# RF_And_SD_Ticketing_Master.net
KiCad netlist of a schematic drawn in Altium Designer
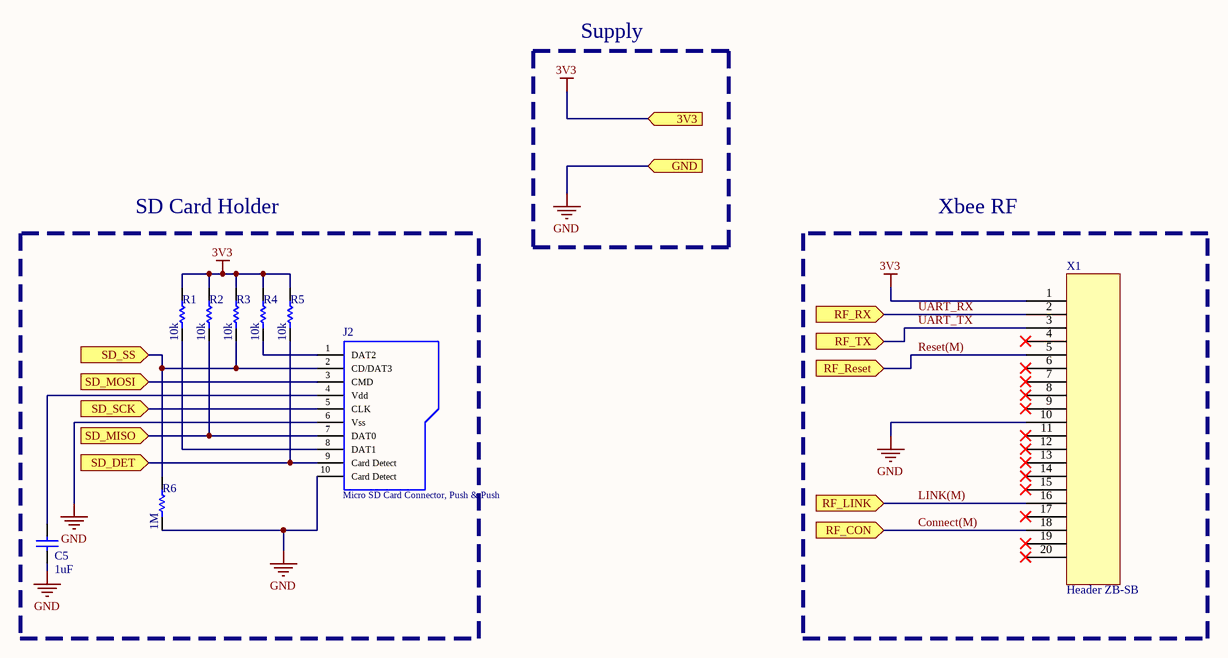
[diagram p0: RF_And_SD_Ticketing_Master.SchDoc]

(export (version "E")
  (design (tool "Eeschema 10.0.6"))
  (components
    (comp (ref "C5")
      (value "1uF")
      (footprint "6-0805_N")
      (description "CAP 10uF 16V ±20% 0805 (2012 Metric) Thickness 1mm SMD")
      (fields (field (name "TOLERANCE") "Â±20%"))
      (libsource (lib "Altium Content Vault") (part "CAP"))
    )
    (comp (ref "J2")
      (value "Micro SD Card Connector, Push & Push")
      (footprint "693071010811")
      (description "WR-CRD Micro SD Card Connector, Push & Push, with card detection")
      (fields (field (name "PART NUMBER") "693071010811") (field (name "PUBLISHER") "Wurth Elektronik"))
      (libsource (lib "ALTIUM-WR-CRD-rev18a") (part "693071010811"))
    )
    (comp (ref "R1")
      (value "10k")
      (footprint "RESC0805(2012)_L")
      (description "100K 0.125W 5% 0805 (2012 Metric)  SMD")
      (fields (field (name "TOLERANCE") "5 %") (field (name "POWER") "0.125 W"))
      (libsource (lib "Altium Content Vault") (part "CMP-1013-00122-1"))
    )
    (comp (ref "R2")
      (value "10k")
      (footprint "RESC0805(2012)_L")
      (description "100K 0.125W 5% 0805 (2012 Metric)  SMD")
      (fields (field (name "TOLERANCE") "5 %") (field (name "POWER") "0.125 W"))
      (libsource (lib "Altium Content Vault") (part "CMP-1013-00122-1"))
    )
    (comp (ref "R3")
      (value "10k")
      (footprint "RESC0805(2012)_L")
      (description "100K 0.125W 5% 0805 (2012 Metric)  SMD")
      (fields (field (name "TOLERANCE") "5 %") (field (name "POWER") "0.125 W"))
      (libsource (lib "Altium Content Vault") (part "CMP-1013-00122-1"))
    )
    (comp (ref "R4")
      (value "10k")
      (footprint "RESC0805(2012)_L")
      (description "100K 0.125W 5% 0805 (2012 Metric)  SMD")
      (fields (field (name "TOLERANCE") "5 %") (field (name "POWER") "0.125 W"))
      (libsource (lib "Altium Content Vault") (part "CMP-1013-00122-1"))
    )
    (comp (ref "R5")
      (value "10k")
      (footprint "RESC0805(2012)_L")
      (description "100K 0.125W 5% 0805 (2012 Metric)  SMD")
      (fields (field (name "TOLERANCE") "5 %") (field (name "POWER") "0.125 W"))
      (libsource (lib "Altium Content Vault") (part "CMP-1013-00122-1"))
    )
    (comp (ref "R6")
      (value "1M")
      (footprint "RESC0805(2012)_L")
      (description "100K 0.125W 5% 0805 (2012 Metric)  SMD")
      (fields (field (name "TOLERANCE") "5 %") (field (name "POWER") "0.125 W"))
      (libsource (lib "Altium Content Vault") (part "CMP-1013-00122-1"))
    )
    (comp (ref "X1")
      (value "Header ZB-SB")
      (footprint "ZB-SB")
      (description "Header 2x10")
      (libsource (lib "CircuitOUT") (part "HDR ZB-SB 2x10"))
    )
  )
  (nets
    (net (code "1") (name "/Connect(M)") (class "Default") (node (ref "X1") (pin "18") (pintype "passive")))
    (net (code "2") (name "/LINK(M)") (class "Default") (node (ref "X1") (pin "16") (pintype "passive")))
    (net (code "3") (name "/Reset(M)") (class "Default") (node (ref "X1") (pin "5") (pintype "passive")))
    (net (code "4") (name "/SD_DET") (class "Default")
      (node (ref "J2") (pin "9") (pinfunction "Card_Detect_9") (pintype "passive"))
      (node (ref "R5") (pin "1") (pinfunction "1_1") (pintype "passive"))
    )
    (net (code "5") (name "/SD_MISO") (class "Default")
      (node (ref "J2") (pin "7") (pinfunction "DAT0_7") (pintype "passive"))
      (node (ref "R2") (pin "1") (pinfunction "1_1") (pintype "passive"))
    )
    (net (code "6") (name "/SD_MOSI") (class "Default")
      (node (ref "J2") (pin "3") (pinfunction "CMD_3") (pintype "passive"))
    )
    (net (code "7") (name "/SD_SCK") (class "Default")
      (node (ref "J2") (pin "5") (pinfunction "CLK_5") (pintype "passive"))
    )
    (net (code "8") (name "/SD_SS") (class "Default")
      (node (ref "J2") (pin "2") (pinfunction "CD/DAT3_2") (pintype "passive"))
      (node (ref "R3") (pin "1") (pinfunction "1_1") (pintype "passive"))
      (node (ref "R6") (pin "2") (pinfunction "2_2") (pintype "passive"))
    )
    (net (code "9") (name "/UART_RX") (class "Default") (node (ref "X1") (pin "2") (pintype "passive")))
    (net (code "10") (name "/UART_TX") (class "Default") (node (ref "X1") (pin "3") (pintype "passive")))
    (net (code "11") (name "3V3") (class "Default")
      (node (ref "R1") (pin "2") (pinfunction "2_2") (pintype "passive"))
      (node (ref "R2") (pin "2") (pinfunction "2_2") (pintype "passive"))
      (node (ref "R3") (pin "2") (pinfunction "2_2") (pintype "passive"))
      (node (ref "R4") (pin "2") (pinfunction "2_2") (pintype "passive"))
      (node (ref "R5") (pin "2") (pinfunction "2_2") (pintype "passive"))
      (node (ref "X1") (pin "1") (pintype "passive"))
    )
    (net (code "12") (name "GND") (class "Default")
      (node (ref "C5") (pin "1") (pinfunction "1_1") (pintype "passive"))
      (node (ref "J2") (pin "10") (pinfunction "Card_Detect_10") (pintype "passive"))
      (node (ref "J2") (pin "6") (pinfunction "Vss_6") (pintype "passive"))
      (node (ref "R6") (pin "1") (pinfunction "1_1") (pintype "passive"))
      (node (ref "X1") (pin "10") (pintype "passive"))
    )
    (net (code "13") (name "Net-(J2-DAT1)") (class "Default")
      (node (ref "J2") (pin "8") (pinfunction "DAT1_8") (pintype "passive"))
      (node (ref "R1") (pin "1") (pinfunction "1_1") (pintype "passive"))
    )
    (net (code "14") (name "Net-(J2-DAT2)") (class "Default")
      (node (ref "J2") (pin "1") (pinfunction "DAT2_1") (pintype "passive"))
      (node (ref "R4") (pin "1") (pinfunction "1_1") (pintype "passive"))
    )
    (net (code "15") (name "Net-(J2-Vdd)") (class "Default")
      (node (ref "C5") (pin "2") (pinfunction "2_2") (pintype "passive"))
      (node (ref "J2") (pin "4") (pinfunction "Vdd_4") (pintype "passive"))
    )
    (net (code "16") (name "unconnected-(X1-Pad4)") (class "Default")
      (node (ref "X1") (pin "4") (pintype "passive+no_connect"))
    )
    (net (code "17") (name "unconnected-(X1-Pad6)") (class "Default")
      (node (ref "X1") (pin "6") (pintype "passive+no_connect"))
    )
    (net (code "18") (name "unconnected-(X1-Pad7)") (class "Default")
      (node (ref "X1") (pin "7") (pintype "passive+no_connect"))
    )
    (net (code "19") (name "unconnected-(X1-Pad8)") (class "Default")
      (node (ref "X1") (pin "8") (pintype "passive+no_connect"))
    )
    (net (code "20") (name "unconnected-(X1-Pad9)") (class "Default")
      (node (ref "X1") (pin "9") (pintype "passive+no_connect"))
    )
    (net (code "21") (name "unconnected-(X1-Pad11)") (class "Default")
      (node (ref "X1") (pin "11") (pintype "passive+no_connect"))
    )
    (net (code "22") (name "unconnected-(X1-Pad12)") (class "Default")
      (node (ref "X1") (pin "12") (pintype "passive+no_connect"))
    )
    (net (code "23") (name "unconnected-(X1-Pad13)") (class "Default")
      (node (ref "X1") (pin "13") (pintype "passive+no_connect"))
    )
    (net (code "24") (name "unconnected-(X1-Pad14)") (class "Default")
      (node (ref "X1") (pin "14") (pintype "passive+no_connect"))
    )
    (net (code "25") (name "unconnected-(X1-Pad15)") (class "Default")
      (node (ref "X1") (pin "15") (pintype "passive+no_connect"))
    )
    (net (code "26") (name "unconnected-(X1-Pad17)") (class "Default")
      (node (ref "X1") (pin "17") (pintype "passive+no_connect"))
    )
    (net (code "27") (name "unconnected-(X1-Pad19)") (class "Default")
      (node (ref "X1") (pin "19") (pintype "passive+no_connect"))
    )
    (net (code "28") (name "unconnected-(X1-Pad20)") (class "Default")
      (node (ref "X1") (pin "20") (pintype "passive+no_connect"))
    )
  )
)
